# SparkFun_IMU_Fusion_Board.net
KiCad netlist of a schematic drawn in EAGLE
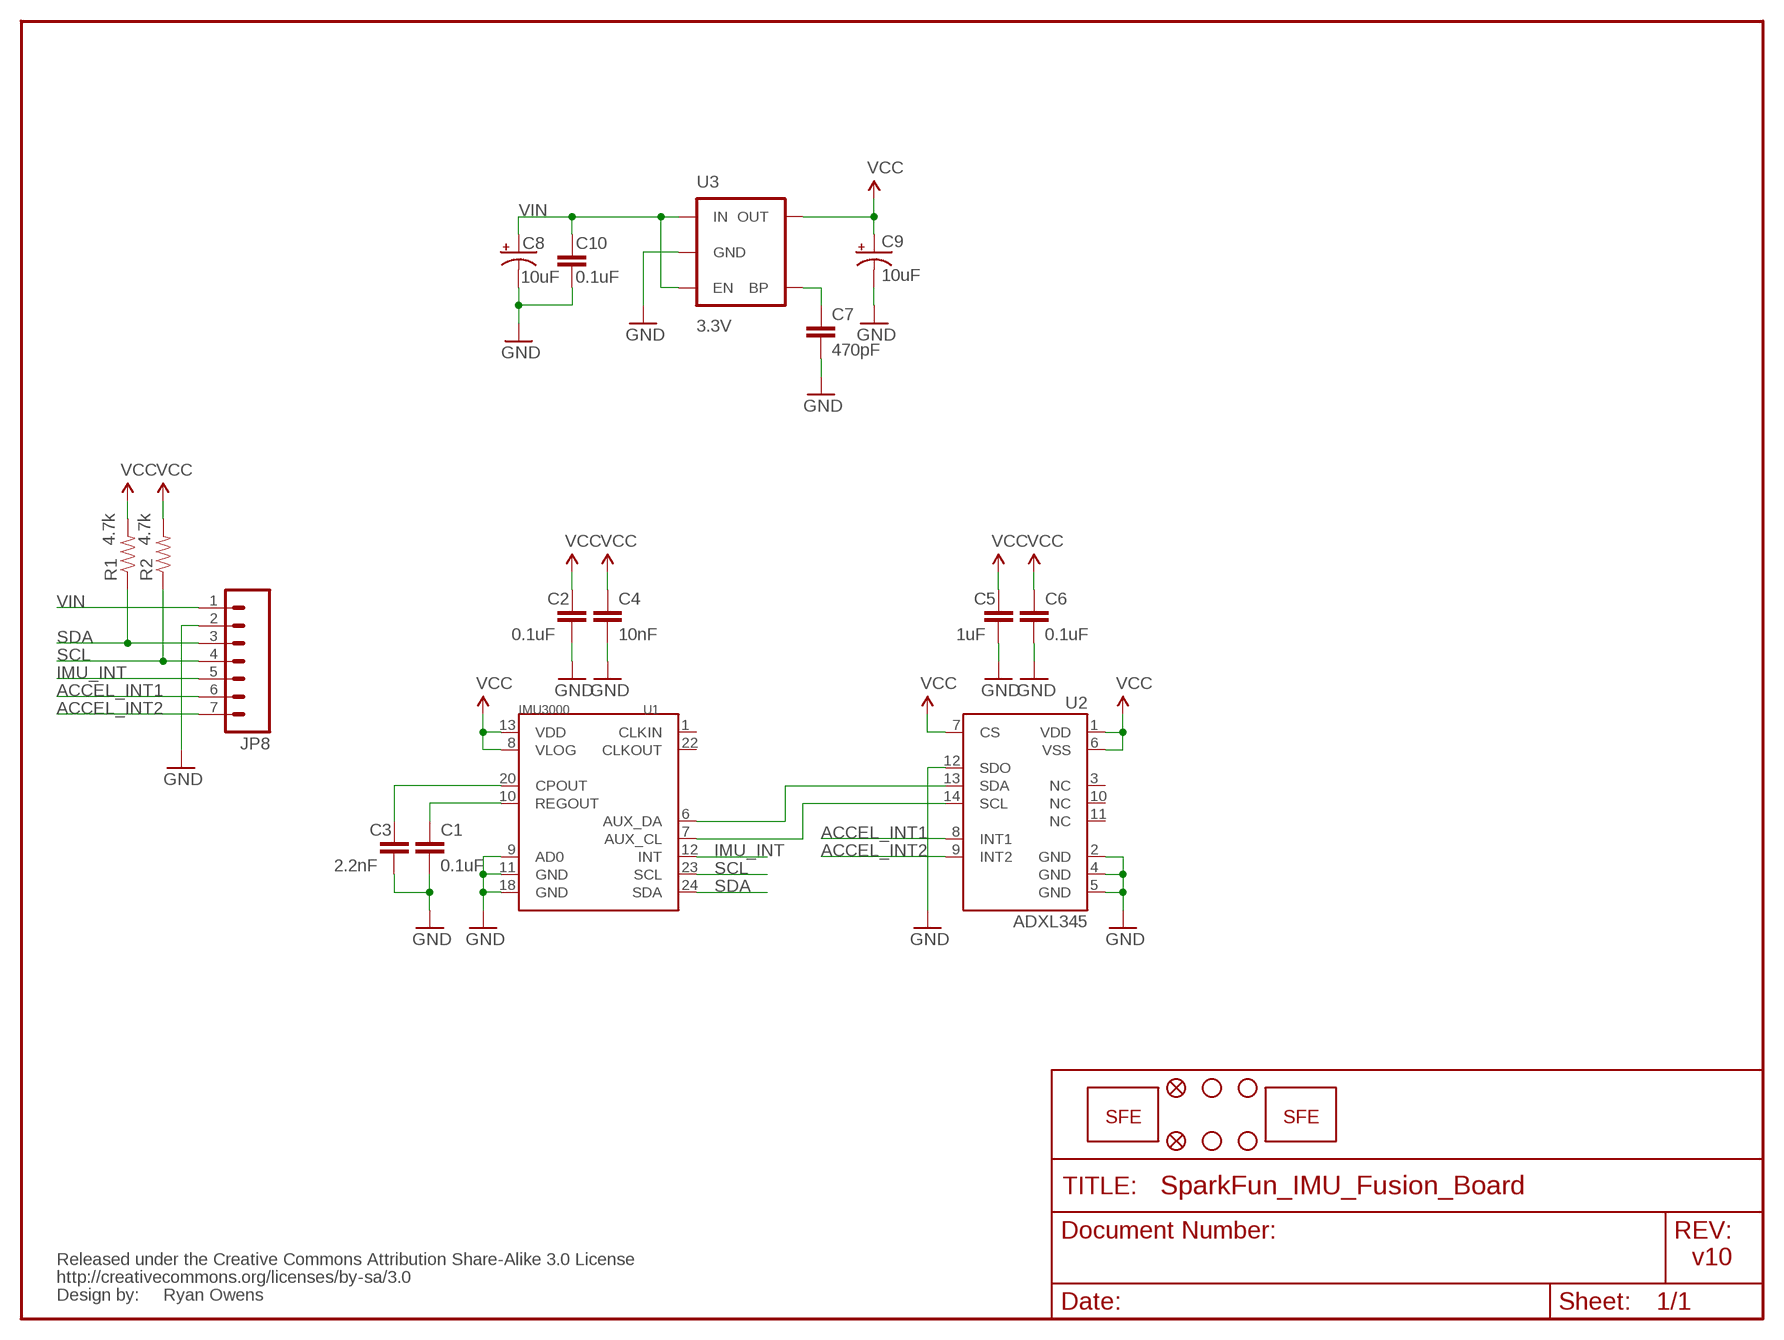
[diagram p0: schematic, sheet 1]

(export (version "E")
  (design (tool "Eeschema 10.0.6"))
  (components
    (comp (ref "C1")
      (value "0.1uF")
      (footprint "eagle-import:0603-CAP")
      (libsource (lib "eagle-import") (part "CAP0603-CAP"))
    )
    (comp (ref "C2")
      (value "0.1uF")
      (footprint "eagle-import:0603-CAP")
      (libsource (lib "eagle-import") (part "CAP0603-CAP"))
    )
    (comp (ref "C3")
      (value "2.2nF")
      (footprint "eagle-import:0603-CAP")
      (libsource (lib "eagle-import") (part "CAP0603-CAP"))
    )
    (comp (ref "C4")
      (value "10nF")
      (footprint "eagle-import:0603-CAP")
      (libsource (lib "eagle-import") (part "CAP0603-CAP"))
    )
    (comp (ref "C5")
      (value "1uF")
      (footprint "eagle-import:0603-CAP")
      (libsource (lib "eagle-import") (part "CAP0603-CAP"))
    )
    (comp (ref "C6")
      (value "0.1uF")
      (footprint "eagle-import:0603-CAP")
      (libsource (lib "eagle-import") (part "CAP0603-CAP"))
    )
    (comp (ref "C7")
      (value "470pF")
      (footprint "eagle-import:0603-CAP")
      (libsource (lib "eagle-import") (part "CAP0603-CAP"))
    )
    (comp (ref "C8")
      (value "10uF")
      (footprint "eagle-import:EIA3216")
      (libsource (lib "eagle-import") (part "CAP_POL1206"))
    )
    (comp (ref "C9")
      (value "10uF")
      (footprint "eagle-import:EIA3216")
      (libsource (lib "eagle-import") (part "CAP_POL1206"))
    )
    (comp (ref "C10")
      (value "0.1uF")
      (footprint "eagle-import:0603-CAP")
      (libsource (lib "eagle-import") (part "CAP0603-CAP"))
    )
    (comp (ref "JP1")
      (value "LOGO-SFENEW")
      (footprint "eagle-import:SFE-NEW-WEBLOGO")
      (libsource (lib "eagle-import") (part "LOGO-SFENEW"))
    )
    (comp (ref "JP2")
      (value "FIDUCIAL1X2")
      (footprint "eagle-import:FIDUCIAL-1X2")
      (libsource (lib "eagle-import") (part "FIDUCIAL1X2"))
    )
    (comp (ref "JP3")
      (value "FIDUCIAL1X2")
      (footprint "eagle-import:FIDUCIAL-1X2")
      (libsource (lib "eagle-import") (part "FIDUCIAL1X2"))
    )
    (comp (ref "JP4")
      (value "STAND-OFF")
      (footprint "eagle-import:STAND-OFF")
      (libsource (lib "eagle-import") (part "STAND-OFF"))
    )
    (comp (ref "JP5")
      (value "STAND-OFF")
      (footprint "eagle-import:STAND-OFF")
      (libsource (lib "eagle-import") (part "STAND-OFF"))
    )
    (comp (ref "JP6")
      (value "STAND-OFF")
      (footprint "eagle-import:STAND-OFF")
      (libsource (lib "eagle-import") (part "STAND-OFF"))
    )
    (comp (ref "JP7")
      (value "STAND-OFF")
      (footprint "eagle-import:STAND-OFF")
      (libsource (lib "eagle-import") (part "STAND-OFF"))
    )
    (comp (ref "JP8")
      (value "M07")
      (footprint "eagle-import:1X07")
      (libsource (lib "eagle-import") (part "M07"))
    )
    (comp (ref "JP9")
      (value "LOGO-SFESK")
      (footprint "eagle-import:SFE-LOGO-FLAME")
      (libsource (lib "eagle-import") (part "LOGO-SFESK"))
    )
    (comp (ref "R1")
      (value "4.7k")
      (footprint "eagle-import:0603-RES")
      (libsource (lib "eagle-import") (part "RESISTOR0603-RES"))
    )
    (comp (ref "R2")
      (value "4.7k")
      (footprint "eagle-import:0603-RES")
      (libsource (lib "eagle-import") (part "RESISTOR0603-RES"))
    )
    (comp (ref "U$1")
      (value "CREATIVE_COMMONS")
      (footprint "eagle-import:CREATIVE_COMMONS")
      (libsource (lib "eagle-import") (part "CREATIVE_COMMONS"))
    )
    (comp (ref "U1")
      (value "IMU3000")
      (footprint "eagle-import:QFN-24")
      (libsource (lib "eagle-import") (part "IMU3000"))
    )
    (comp (ref "U2")
      (value "ADXL345")
      (footprint "eagle-import:LGA14")
      (libsource (lib "eagle-import") (part "ADXL345"))
    )
    (comp (ref "U3")
      (value "3.3V")
      (footprint "eagle-import:SOT23-5")
      (libsource (lib "eagle-import") (part "V_REG_LDOSMD"))
    )
  )
  (nets
    (net (code "1") (name "/ACCEL_INT1") (class "Default")
      (node (ref "JP8") (pin "6") (pinfunction "6_6") (pintype "passive"))
      (node (ref "U2") (pin "8") (pinfunction "INT1_8") (pintype "bidirectional"))
    )
    (net (code "2") (name "/ACCEL_INT2") (class "Default")
      (node (ref "JP8") (pin "7") (pinfunction "7_7") (pintype "passive"))
      (node (ref "U2") (pin "9") (pinfunction "INT2_9") (pintype "bidirectional"))
    )
    (net (code "3") (name "/IMU_INT") (class "Default")
      (node (ref "JP8") (pin "5") (pinfunction "5_5") (pintype "passive"))
      (node (ref "U1") (pin "12") (pinfunction "INT_12") (pintype "bidirectional"))
    )
    (net (code "4") (name "/SCL") (class "Default")
      (node (ref "JP8") (pin "4") (pinfunction "4_4") (pintype "passive"))
      (node (ref "R2") (pin "1") (pinfunction "1_1") (pintype "passive"))
      (node (ref "U1") (pin "23") (pinfunction "SCL_23") (pintype "bidirectional"))
    )
    (net (code "5") (name "/SDA") (class "Default")
      (node (ref "JP8") (pin "3") (pinfunction "3_3") (pintype "passive"))
      (node (ref "R1") (pin "1") (pinfunction "1_1") (pintype "passive"))
      (node (ref "U1") (pin "24") (pinfunction "SDA_24") (pintype "bidirectional"))
    )
    (net (code "6") (name "/VIN") (class "Default")
      (node (ref "C10") (pin "1") (pinfunction "1_1") (pintype "passive"))
      (node (ref "C8") (pin "A") (pinfunction "+_A") (pintype "passive"))
      (node (ref "JP8") (pin "1") (pinfunction "1_1") (pintype "passive"))
      (node (ref "U3") (pin "1") (pinfunction "IN_1") (pintype "input"))
      (node (ref "U3") (pin "3") (pinfunction "EN_3") (pintype "input"))
    )
    (net (code "7") (name "GND") (class "Default")
      (node (ref "C1") (pin "2") (pinfunction "2_2") (pintype "passive"))
      (node (ref "C10") (pin "2") (pinfunction "2_2") (pintype "passive"))
      (node (ref "C2") (pin "2") (pinfunction "2_2") (pintype "passive"))
      (node (ref "C3") (pin "2") (pinfunction "2_2") (pintype "passive"))
      (node (ref "C4") (pin "2") (pinfunction "2_2") (pintype "passive"))
      (node (ref "C5") (pin "2") (pinfunction "2_2") (pintype "passive"))
      (node (ref "C6") (pin "2") (pinfunction "2_2") (pintype "passive"))
      (node (ref "C7") (pin "2") (pinfunction "2_2") (pintype "passive"))
      (node (ref "C8") (pin "C") (pinfunction "-_C") (pintype "passive"))
      (node (ref "C9") (pin "C") (pinfunction "-_C") (pintype "passive"))
      (node (ref "JP8") (pin "2") (pinfunction "2_2") (pintype "passive"))
      (node (ref "U1") (pin "11") (pinfunction "GND_11") (pintype "bidirectional"))
      (node (ref "U1") (pin "18") (pinfunction "GND_18") (pintype "bidirectional"))
      (node (ref "U1") (pin "9") (pinfunction "AD0_9") (pintype "bidirectional"))
      (node (ref "U2") (pin "12") (pinfunction "SDO_12") (pintype "bidirectional"))
      (node (ref "U2") (pin "2") (pinfunction "GND_2") (pintype "bidirectional"))
      (node (ref "U2") (pin "4") (pinfunction "GND_4") (pintype "bidirectional"))
      (node (ref "U2") (pin "5") (pinfunction "GND_5") (pintype "bidirectional"))
      (node (ref "U3") (pin "2") (pinfunction "GND_2") (pintype "input"))
    )
    (net (code "8") (name "Net-(U1-AUX_CL)") (class "Default")
      (node (ref "U1") (pin "7") (pinfunction "AUX_CL_7") (pintype "bidirectional"))
      (node (ref "U2") (pin "14") (pinfunction "SCL_14") (pintype "bidirectional"))
    )
    (net (code "9") (name "Net-(U1-AUX_DA)") (class "Default")
      (node (ref "U1") (pin "6") (pinfunction "AUX_DA_6") (pintype "bidirectional"))
      (node (ref "U2") (pin "13") (pinfunction "SDA_13") (pintype "bidirectional"))
    )
    (net (code "10") (name "Net-(U1-CPOUT)") (class "Default")
      (node (ref "C3") (pin "1") (pinfunction "1_1") (pintype "passive"))
      (node (ref "U1") (pin "20") (pinfunction "CPOUT_20") (pintype "bidirectional"))
    )
    (net (code "11") (name "Net-(U1-REGOUT)") (class "Default")
      (node (ref "C1") (pin "1") (pinfunction "1_1") (pintype "passive"))
      (node (ref "U1") (pin "10") (pinfunction "REGOUT_10") (pintype "bidirectional"))
    )
    (net (code "12") (name "Net-(U3-BP)") (class "Default")
      (node (ref "C7") (pin "1") (pinfunction "1_1") (pintype "passive"))
      (node (ref "U3") (pin "4") (pinfunction "BP_4") (pintype "input"))
    )
    (net (code "13") (name "VCC") (class "Default")
      (node (ref "C2") (pin "1") (pinfunction "1_1") (pintype "passive"))
      (node (ref "C4") (pin "1") (pinfunction "1_1") (pintype "passive"))
      (node (ref "C5") (pin "1") (pinfunction "1_1") (pintype "passive"))
      (node (ref "C6") (pin "1") (pinfunction "1_1") (pintype "passive"))
      (node (ref "C9") (pin "A") (pinfunction "+_A") (pintype "passive"))
      (node (ref "R1") (pin "2") (pinfunction "2_2") (pintype "passive"))
      (node (ref "R2") (pin "2") (pinfunction "2_2") (pintype "passive"))
      (node (ref "U1") (pin "13") (pinfunction "VDD_13") (pintype "bidirectional"))
      (node (ref "U1") (pin "8") (pinfunction "VLOG_8") (pintype "bidirectional"))
      (node (ref "U2") (pin "1") (pinfunction "VDD_1") (pintype "bidirectional"))
      (node (ref "U2") (pin "6") (pinfunction "VSS_6") (pintype "bidirectional"))
      (node (ref "U2") (pin "7") (pinfunction "CS_7") (pintype "bidirectional"))
      (node (ref "U3") (pin "5") (pinfunction "OUT_5") (pintype "passive"))
    )
    (net (code "14") (name "unconnected-(U1-CLKIN-Pad1)") (class "Default")
      (node (ref "U1") (pin "1") (pinfunction "CLKIN_1") (pintype "bidirectional"))
    )
    (net (code "15") (name "unconnected-(U1-CLKOUT-Pad22)") (class "Default")
      (node (ref "U1") (pin "22") (pinfunction "CLKOUT_22") (pintype "bidirectional"))
    )
    (net (code "16") (name "unconnected-(U2-NC-Pad3)") (class "Default")
      (node (ref "U2") (pin "3") (pinfunction "NC_3") (pintype "bidirectional"))
    )
    (net (code "17") (name "unconnected-(U2-NC-Pad10)") (class "Default")
      (node (ref "U2") (pin "10") (pinfunction "NC_10") (pintype "bidirectional"))
    )
    (net (code "18") (name "unconnected-(U2-NC-Pad11)") (class "Default")
      (node (ref "U2") (pin "11") (pinfunction "NC_11") (pintype "bidirectional"))
    )
  )
)
